# platform_smd.net
KiCad netlist of a schematic drawn in EAGLE
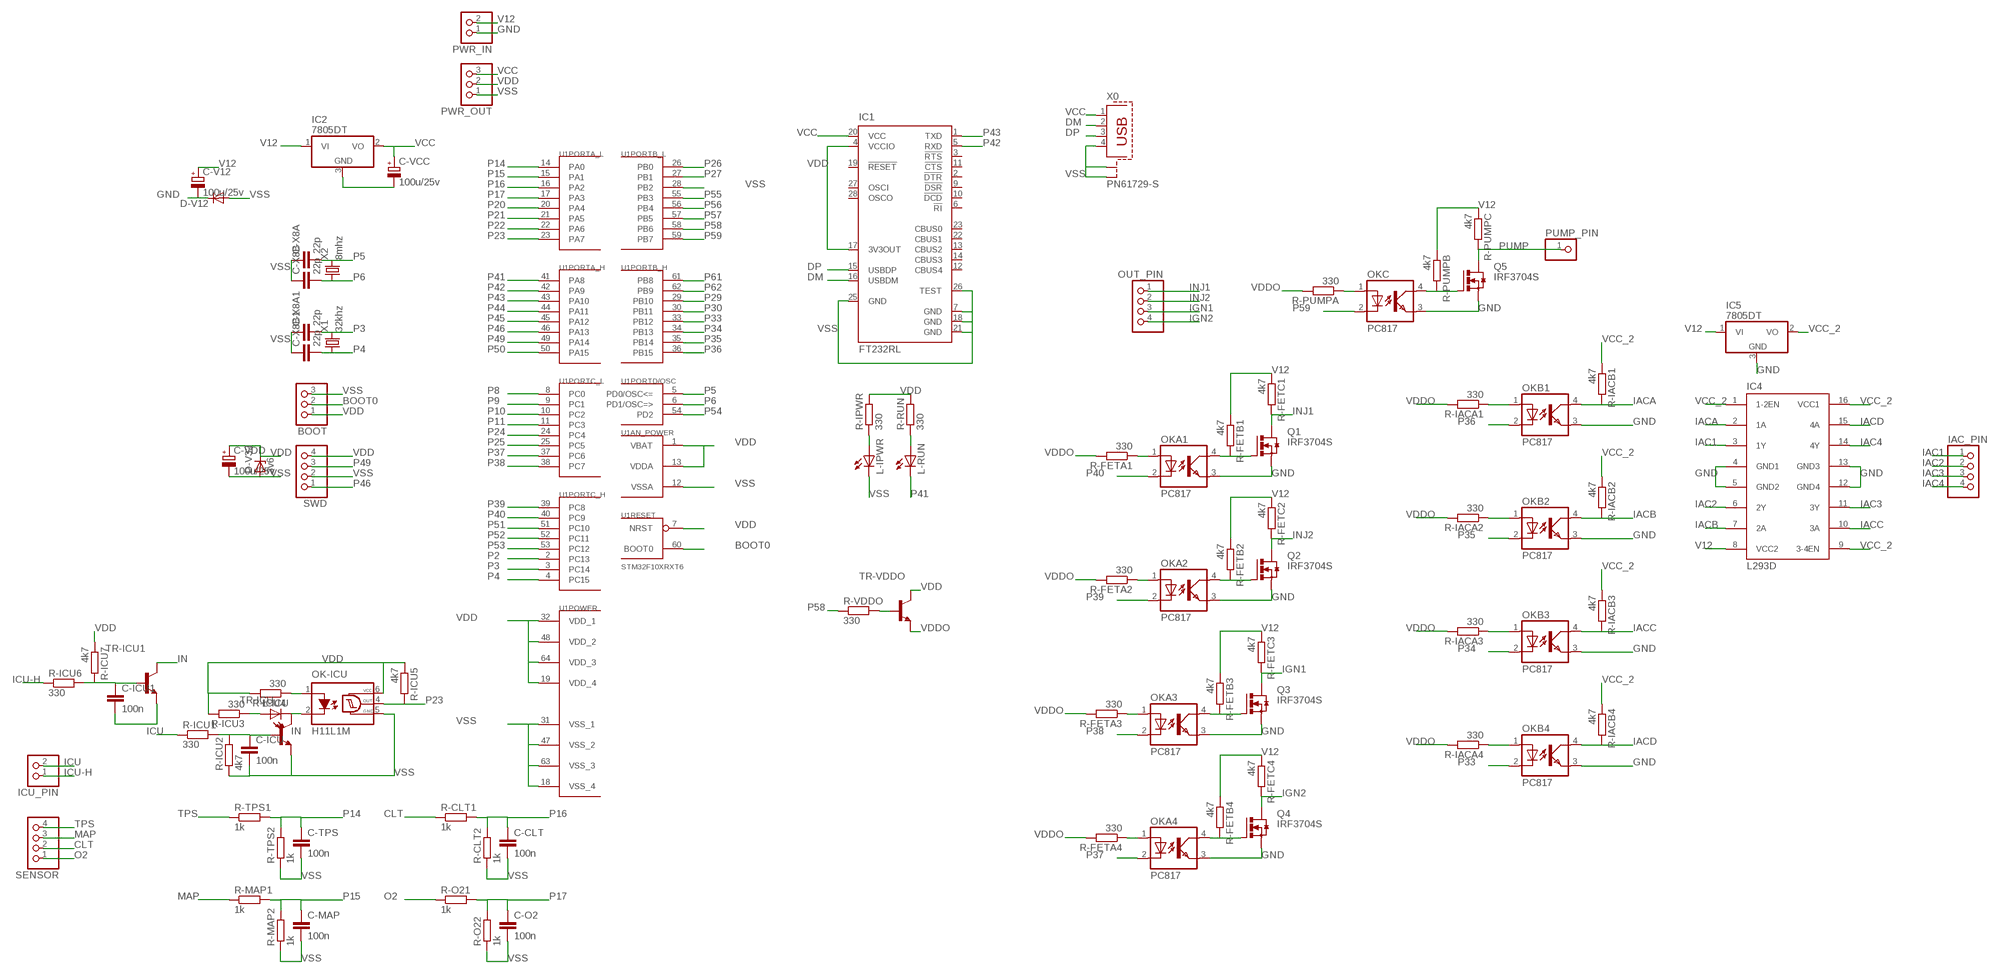
[diagram p0: schematic, sheet 1]

(export (version "E")
  (design (tool "Eeschema 10.0.6"))
  (components
    (comp (ref "BOOT")
      (value "PINHD-1X3")
      (footprint "eagle-import:1X03")
      (libsource (lib "eagle-import") (part "PINHD-1X3"))
    )
    (comp (ref "C-CLT")
      (value "100n")
      (footprint "eagle-import:C0805")
      (libsource (lib "eagle-import") (part "C-EUC0805"))
    )
    (comp (ref "C-ICU")
      (value "100n")
      (footprint "eagle-import:C0805")
      (libsource (lib "eagle-import") (part "C-EUC0805"))
    )
    (comp (ref "C-ICU1")
      (value "100n")
      (footprint "eagle-import:C0805")
      (libsource (lib "eagle-import") (part "C-EUC0805"))
    )
    (comp (ref "C-MAP")
      (value "100n")
      (footprint "eagle-import:C0805")
      (libsource (lib "eagle-import") (part "C-EUC0805"))
    )
    (comp (ref "C-O2")
      (value "100n")
      (footprint "eagle-import:C0805")
      (libsource (lib "eagle-import") (part "C-EUC0805"))
    )
    (comp (ref "C-TPS")
      (value "100n")
      (footprint "eagle-import:C0805")
      (libsource (lib "eagle-import") (part "C-EUC0805"))
    )
    (comp (ref "C-V12")
      (value "100u/25v")
      (footprint "eagle-import:PANASONIC_D")
      (libsource (lib "eagle-import") (part "CPOL-EUD"))
    )
    (comp (ref "C-VCC")
      (value "100u/25v")
      (footprint "eagle-import:PANASONIC_D")
      (libsource (lib "eagle-import") (part "CPOL-EUD"))
    )
    (comp (ref "C-VDD")
      (value "100u/25v")
      (footprint "eagle-import:PANASONIC_D")
      (libsource (lib "eagle-import") (part "CPOL-EUD"))
    )
    (comp (ref "C-X8A")
      (value "22p")
      (footprint "eagle-import:C0805")
      (libsource (lib "eagle-import") (part "C-EUC0805"))
    )
    (comp (ref "C-X8A1")
      (value "22p")
      (footprint "eagle-import:C0805")
      (libsource (lib "eagle-import") (part "C-EUC0805"))
    )
    (comp (ref "C-X8B")
      (value "22p")
      (footprint "eagle-import:C0805")
      (libsource (lib "eagle-import") (part "C-EUC0805"))
    )
    (comp (ref "C-X8B1")
      (value "22p")
      (footprint "eagle-import:C0805")
      (libsource (lib "eagle-import") (part "C-EUC0805"))
    )
    (comp (ref "D-V12")
      (value "DIODE-SMB")
      (footprint "eagle-import:SMB")
      (libsource (lib "eagle-import") (part "DIODE-SMB"))
    )
    (comp (ref "D-V33")
      (value "3v6")
      (footprint "eagle-import:SMB")
      (libsource (lib "eagle-import") (part "ZENER-DIODESMB"))
    )
    (comp (ref "IAC_PIN")
      (value "PINHD-1X4")
      (footprint "eagle-import:1X04")
      (libsource (lib "eagle-import") (part "PINHD-1X4"))
    )
    (comp (ref "IC1")
      (value "FT232RL")
      (footprint "eagle-import:SSOP28")
      (libsource (lib "eagle-import") (part "FT232RL"))
    )
    (comp (ref "IC2")
      (value "7805DT")
      (footprint "eagle-import:TO252")
      (libsource (lib "eagle-import") (part "78DT05"))
    )
    (comp (ref "IC4")
      (value "L293D")
      (footprint "eagle-import:DIL16")
      (libsource (lib "eagle-import") (part "L293D"))
    )
    (comp (ref "IC5")
      (value "7805DT")
      (footprint "eagle-import:TO252")
      (libsource (lib "eagle-import") (part "78DT05"))
    )
    (comp (ref "ICU_PIN")
      (value "PINHD-1X2")
      (footprint "eagle-import:1X02")
      (libsource (lib "eagle-import") (part "PINHD-1X2"))
    )
    (comp (ref "L-ICU")
      (value "LEDSML0805")
      (footprint "eagle-import:SML0805")
      (libsource (lib "eagle-import") (part "LEDSML0805"))
    )
    (comp (ref "L-IPWR")
      (value "LEDSML0805")
      (footprint "eagle-import:SML0805")
      (libsource (lib "eagle-import") (part "LEDSML0805"))
    )
    (comp (ref "L-RUN")
      (value "LEDSML0805")
      (footprint "eagle-import:SML0805")
      (libsource (lib "eagle-import") (part "LEDSML0805"))
    )
    (comp (ref "OK-ICU")
      (value "H11L1M")
      (footprint "eagle-import:DIL06")
      (fields (field (name "MF") "FAIRCHILD SEMICONDUCTOR") (field (name "MPN") "H11L1-M"))
      (libsource (lib "eagle-import") (part "H11LM1"))
    )
    (comp (ref "OKA1")
      (value "PC817")
      (footprint "eagle-import:DIL04")
      (fields (field (name "MPN") "PC817X4J000F"))
      (libsource (lib "eagle-import") (part "PC817"))
    )
    (comp (ref "OKA2")
      (value "PC817")
      (footprint "eagle-import:DIL04")
      (fields (field (name "MPN") "PC817X4J000F"))
      (libsource (lib "eagle-import") (part "PC817"))
    )
    (comp (ref "OKA3")
      (value "PC817")
      (footprint "eagle-import:DIL04")
      (fields (field (name "MPN") "PC817X4J000F"))
      (libsource (lib "eagle-import") (part "PC817"))
    )
    (comp (ref "OKA4")
      (value "PC817")
      (footprint "eagle-import:DIL04")
      (fields (field (name "MPN") "PC817X4J000F"))
      (libsource (lib "eagle-import") (part "PC817"))
    )
    (comp (ref "OKB1")
      (value "PC817")
      (footprint "eagle-import:DIL04")
      (fields (field (name "MPN") "PC817X4J000F"))
      (libsource (lib "eagle-import") (part "PC817"))
    )
    (comp (ref "OKB2")
      (value "PC817")
      (footprint "eagle-import:DIL04")
      (fields (field (name "MPN") "PC817X4J000F"))
      (libsource (lib "eagle-import") (part "PC817"))
    )
    (comp (ref "OKB3")
      (value "PC817")
      (footprint "eagle-import:DIL04")
      (fields (field (name "MPN") "PC817X4J000F"))
      (libsource (lib "eagle-import") (part "PC817"))
    )
    (comp (ref "OKB4")
      (value "PC817")
      (footprint "eagle-import:DIL04")
      (fields (field (name "MPN") "PC817X4J000F"))
      (libsource (lib "eagle-import") (part "PC817"))
    )
    (comp (ref "OKC")
      (value "PC817")
      (footprint "eagle-import:DIL04")
      (fields (field (name "MPN") "PC817X4J000F"))
      (libsource (lib "eagle-import") (part "PC817"))
    )
    (comp (ref "OUT_PIN")
      (value "PINHD-1X4")
      (footprint "eagle-import:1X04")
      (libsource (lib "eagle-import") (part "PINHD-1X4"))
    )
    (comp (ref "PUMP_PIN")
      (value "PINHD-1X1")
      (footprint "eagle-import:1X01")
      (libsource (lib "eagle-import") (part "PINHD-1X1"))
    )
    (comp (ref "PWR_IN")
      (value "PINHD-1X2")
      (footprint "eagle-import:1X02")
      (libsource (lib "eagle-import") (part "PINHD-1X2"))
    )
    (comp (ref "PWR_OUT")
      (value "PINHD-1X3")
      (footprint "eagle-import:1X03")
      (libsource (lib "eagle-import") (part "PINHD-1X3"))
    )
    (comp (ref "Q1")
      (value "IRF3704S")
      (footprint "eagle-import:D2PACK")
      (libsource (lib "eagle-import") (part "IRF3704S"))
    )
    (comp (ref "Q2")
      (value "IRF3704S")
      (footprint "eagle-import:D2PACK")
      (libsource (lib "eagle-import") (part "IRF3704S"))
    )
    (comp (ref "Q3")
      (value "IRF3704S")
      (footprint "eagle-import:D2PACK")
      (libsource (lib "eagle-import") (part "IRF3704S"))
    )
    (comp (ref "Q4")
      (value "IRF3704S")
      (footprint "eagle-import:D2PACK")
      (libsource (lib "eagle-import") (part "IRF3704S"))
    )
    (comp (ref "Q5")
      (value "IRF3704S")
      (footprint "eagle-import:D2PACK")
      (libsource (lib "eagle-import") (part "IRF3704S"))
    )
    (comp (ref "R-CLT1")
      (value "1k")
      (footprint "eagle-import:R0805")
      (libsource (lib "eagle-import") (part "R-EU_R0805"))
    )
    (comp (ref "R-CLT2")
      (value "1k")
      (footprint "eagle-import:R0805")
      (libsource (lib "eagle-import") (part "R-EU_R0805"))
    )
    (comp (ref "R-FETA1")
      (value "330")
      (footprint "eagle-import:R0805")
      (libsource (lib "eagle-import") (part "R-EU_R0805"))
    )
    (comp (ref "R-FETA2")
      (value "330")
      (footprint "eagle-import:R0805")
      (libsource (lib "eagle-import") (part "R-EU_R0805"))
    )
    (comp (ref "R-FETA3")
      (value "330")
      (footprint "eagle-import:R0805")
      (libsource (lib "eagle-import") (part "R-EU_R0805"))
    )
    (comp (ref "R-FETA4")
      (value "330")
      (footprint "eagle-import:R0805")
      (libsource (lib "eagle-import") (part "R-EU_R0805"))
    )
    (comp (ref "R-FETB1")
      (value "4k7")
      (footprint "eagle-import:R0805")
      (libsource (lib "eagle-import") (part "R-EU_R0805"))
    )
    (comp (ref "R-FETB2")
      (value "4k7")
      (footprint "eagle-import:R0805")
      (libsource (lib "eagle-import") (part "R-EU_R0805"))
    )
    (comp (ref "R-FETB3")
      (value "4k7")
      (footprint "eagle-import:R0805")
      (libsource (lib "eagle-import") (part "R-EU_R0805"))
    )
    (comp (ref "R-FETB4")
      (value "4k7")
      (footprint "eagle-import:R0805")
      (libsource (lib "eagle-import") (part "R-EU_R0805"))
    )
    (comp (ref "R-FETC1")
      (value "4k7")
      (footprint "eagle-import:R0805")
      (libsource (lib "eagle-import") (part "R-EU_R0805"))
    )
    (comp (ref "R-FETC2")
      (value "4k7")
      (footprint "eagle-import:R0805")
      (libsource (lib "eagle-import") (part "R-EU_R0805"))
    )
    (comp (ref "R-FETC3")
      (value "4k7")
      (footprint "eagle-import:R0805")
      (libsource (lib "eagle-import") (part "R-EU_R0805"))
    )
    (comp (ref "R-FETC4")
      (value "4k7")
      (footprint "eagle-import:R0805")
      (libsource (lib "eagle-import") (part "R-EU_R0805"))
    )
    (comp (ref "R-IACA1")
      (value "330")
      (footprint "eagle-import:R0805")
      (libsource (lib "eagle-import") (part "R-EU_R0805"))
    )
    (comp (ref "R-IACA2")
      (value "330")
      (footprint "eagle-import:R0805")
      (libsource (lib "eagle-import") (part "R-EU_R0805"))
    )
    (comp (ref "R-IACA3")
      (value "330")
      (footprint "eagle-import:R0805")
      (libsource (lib "eagle-import") (part "R-EU_R0805"))
    )
    (comp (ref "R-IACA4")
      (value "330")
      (footprint "eagle-import:R0805")
      (libsource (lib "eagle-import") (part "R-EU_R0805"))
    )
    (comp (ref "R-IACB1")
      (value "4k7")
      (footprint "eagle-import:R0805")
      (libsource (lib "eagle-import") (part "R-EU_R0805"))
    )
    (comp (ref "R-IACB2")
      (value "4k7")
      (footprint "eagle-import:R0805")
      (libsource (lib "eagle-import") (part "R-EU_R0805"))
    )
    (comp (ref "R-IACB3")
      (value "4k7")
      (footprint "eagle-import:R0805")
      (libsource (lib "eagle-import") (part "R-EU_R0805"))
    )
    (comp (ref "R-IACB4")
      (value "4k7")
      (footprint "eagle-import:R0805")
      (libsource (lib "eagle-import") (part "R-EU_R0805"))
    )
    (comp (ref "R-ICU1")
      (value "330")
      (footprint "eagle-import:R0805")
      (libsource (lib "eagle-import") (part "R-EU_R0805"))
    )
    (comp (ref "R-ICU2")
      (value "4k7")
      (footprint "eagle-import:R0805")
      (libsource (lib "eagle-import") (part "R-EU_R0805"))
    )
    (comp (ref "R-ICU3")
      (value "330")
      (footprint "eagle-import:R0805")
      (libsource (lib "eagle-import") (part "R-EU_R0805"))
    )
    (comp (ref "R-ICU4")
      (value "330")
      (footprint "eagle-import:R0805")
      (libsource (lib "eagle-import") (part "R-EU_R0805"))
    )
    (comp (ref "R-ICU5")
      (value "4k7")
      (footprint "eagle-import:R0805")
      (libsource (lib "eagle-import") (part "R-EU_R0805"))
    )
    (comp (ref "R-ICU6")
      (value "330")
      (footprint "eagle-import:R0805")
      (libsource (lib "eagle-import") (part "R-EU_R0805"))
    )
    (comp (ref "R-ICU7")
      (value "4k7")
      (footprint "eagle-import:R0805")
      (libsource (lib "eagle-import") (part "R-EU_R0805"))
    )
    (comp (ref "R-IPWR")
      (value "330")
      (footprint "eagle-import:R0805")
      (libsource (lib "eagle-import") (part "R-EU_R0805"))
    )
    (comp (ref "R-MAP1")
      (value "1k")
      (footprint "eagle-import:R0805")
      (libsource (lib "eagle-import") (part "R-EU_R0805"))
    )
    (comp (ref "R-MAP2")
      (value "1k")
      (footprint "eagle-import:R0805")
      (libsource (lib "eagle-import") (part "R-EU_R0805"))
    )
    (comp (ref "R-O21")
      (value "1k")
      (footprint "eagle-import:R0805")
      (libsource (lib "eagle-import") (part "R-EU_R0805"))
    )
    (comp (ref "R-O22")
      (value "1k")
      (footprint "eagle-import:R0805")
      (libsource (lib "eagle-import") (part "R-EU_R0805"))
    )
    (comp (ref "R-PUMPA")
      (value "330")
      (footprint "eagle-import:R0805")
      (libsource (lib "eagle-import") (part "R-EU_R0805"))
    )
    (comp (ref "R-PUMPB")
      (value "4k7")
      (footprint "eagle-import:R0805")
      (libsource (lib "eagle-import") (part "R-EU_R0805"))
    )
    (comp (ref "R-PUMPC")
      (value "4k7")
      (footprint "eagle-import:R0805")
      (libsource (lib "eagle-import") (part "R-EU_R0805"))
    )
    (comp (ref "R-RUN")
      (value "330")
      (footprint "eagle-import:R0805")
      (libsource (lib "eagle-import") (part "R-EU_R0805"))
    )
    (comp (ref "R-TPS1")
      (value "1k")
      (footprint "eagle-import:R0805")
      (libsource (lib "eagle-import") (part "R-EU_R0805"))
    )
    (comp (ref "R-TPS2")
      (value "1k")
      (footprint "eagle-import:R0805")
      (libsource (lib "eagle-import") (part "R-EU_R0805"))
    )
    (comp (ref "R-VDDO")
      (value "330")
      (footprint "eagle-import:R0805")
      (libsource (lib "eagle-import") (part "R-EU_R0805"))
    )
    (comp (ref "SENSOR")
      (value "PINHD-1X4")
      (footprint "eagle-import:1X04")
      (libsource (lib "eagle-import") (part "PINHD-1X4"))
    )
    (comp (ref "SWD")
      (value "PINHD-1X4")
      (footprint "eagle-import:1X04")
      (libsource (lib "eagle-import") (part "PINHD-1X4"))
    )
    (comp (ref "TR-ICU")
      (value "MMBT3904LT1-NPN-SOT23-BEC")
      (footprint "eagle-import:SOT23-BEC")
      (libsource (lib "eagle-import") (part "-NPN-SOT23-BECMMBT3904LT1"))
    )
    (comp (ref "TR-ICU1")
      (value "MMBT3904LT1-NPN-SOT23-BEC")
      (footprint "eagle-import:SOT23-BEC")
      (libsource (lib "eagle-import") (part "-NPN-SOT23-BECMMBT3904LT1"))
    )
    (comp (ref "TR-VDDO")
      (value "MMBT3904LT1-NPN-SOT23-BEC")
      (footprint "eagle-import:SOT23-BEC")
      (libsource (lib "eagle-import") (part "-NPN-SOT23-BECMMBT3904LT1"))
    )
    (comp (ref "U1")
      (value "STM32F10XRXT6")
      (footprint "eagle-import:TQFP64")
      (libsource (lib "eagle-import") (part "STM32F10XRXT6"))
    )
    (comp (ref "X0")
      (value "PN61729-S")
      (footprint "eagle-import:PN61729-S")
      (libsource (lib "eagle-import") (part "PN61729-S"))
    )
    (comp (ref "X1")
      (value "32khz")
      (footprint "eagle-import:TC26V")
      (libsource (lib "eagle-import") (part "CRYSTALTC26V"))
    )
    (comp (ref "X2")
      (value "8mhz")
      (footprint "eagle-import:HC49U-V")
      (libsource (lib "eagle-import") (part "CRYSTALHC49U-V"))
    )
  )
  (nets
    (net (code "1") (name "/BOOT0") (class "Default")
      (node (ref "BOOT") (pin "2") (pinfunction "2_2") (pintype "passive"))
      (node (ref "U1") (pin "60") (pinfunction "BOOT0_60") (pintype "input"))
    )
    (net (code "2") (name "/CLT") (class "Default")
      (node (ref "R-CLT1") (pin "1") (pinfunction "1_1") (pintype "passive"))
      (node (ref "SENSOR") (pin "2") (pinfunction "2_2") (pintype "passive"))
    )
    (net (code "3") (name "/DM") (class "Default")
      (node (ref "IC1") (pin "16") (pinfunction "USBDM_16") (pintype "bidirectional"))
      (node (ref "X0") (pin "2") (pinfunction "2_2") (pintype "passive"))
    )
    (net (code "4") (name "/DP") (class "Default")
      (node (ref "IC1") (pin "15") (pinfunction "USBDP_15") (pintype "bidirectional"))
      (node (ref "X0") (pin "3") (pinfunction "3_3") (pintype "passive"))
    )
    (net (code "5") (name "/GND") (class "Default")
      (node (ref "C-V12") (pin "-") (pinfunction "-_-") (pintype "passive"))
      (node (ref "D-V12") (pin "C") (pinfunction "C_C") (pintype "passive"))
      (node (ref "IC4") (pin "12") (pinfunction "GND4_12") (pintype "power_in"))
      (node (ref "IC4") (pin "13") (pinfunction "GND3_13") (pintype "power_in"))
      (node (ref "IC4") (pin "4") (pinfunction "GND1_4") (pintype "power_in"))
      (node (ref "IC4") (pin "5") (pinfunction "GND2_5") (pintype "power_in"))
      (node (ref "IC5") (pin "3") (pinfunction "GND_3") (pintype "passive"))
      (node (ref "OKA1") (pin "3") (pinfunction "EMIT_3") (pintype "passive"))
      (node (ref "OKA2") (pin "3") (pinfunction "EMIT_3") (pintype "passive"))
      (node (ref "OKA3") (pin "3") (pinfunction "EMIT_3") (pintype "passive"))
      (node (ref "OKA4") (pin "3") (pinfunction "EMIT_3") (pintype "passive"))
      (node (ref "OKB1") (pin "3") (pinfunction "EMIT_3") (pintype "passive"))
      (node (ref "OKB2") (pin "3") (pinfunction "EMIT_3") (pintype "passive"))
      (node (ref "OKB3") (pin "3") (pinfunction "EMIT_3") (pintype "passive"))
      (node (ref "OKB4") (pin "3") (pinfunction "EMIT_3") (pintype "passive"))
      (node (ref "OKC") (pin "3") (pinfunction "EMIT_3") (pintype "passive"))
      (node (ref "PWR_IN") (pin "1") (pinfunction "1_1") (pintype "passive"))
      (node (ref "Q1") (pin "3") (pinfunction "S_3") (pintype "passive"))
      (node (ref "Q2") (pin "3") (pinfunction "S_3") (pintype "passive"))
      (node (ref "Q3") (pin "3") (pinfunction "S_3") (pintype "passive"))
      (node (ref "Q4") (pin "3") (pinfunction "S_3") (pintype "passive"))
      (node (ref "Q5") (pin "3") (pinfunction "S_3") (pintype "passive"))
    )
    (net (code "6") (name "/IAC1") (class "Default")
      (node (ref "IAC_PIN") (pin "1") (pinfunction "1_1") (pintype "passive"))
      (node (ref "IC4") (pin "3") (pinfunction "1Y_3") (pintype "output"))
    )
    (net (code "7") (name "/IAC2") (class "Default")
      (node (ref "IAC_PIN") (pin "2") (pinfunction "2_2") (pintype "passive"))
      (node (ref "IC4") (pin "6") (pinfunction "2Y_6") (pintype "output"))
    )
    (net (code "8") (name "/IAC3") (class "Default")
      (node (ref "IAC_PIN") (pin "3") (pinfunction "3_3") (pintype "passive"))
      (node (ref "IC4") (pin "11") (pinfunction "3Y_11") (pintype "output"))
    )
    (net (code "9") (name "/IAC4") (class "Default")
      (node (ref "IAC_PIN") (pin "4") (pinfunction "4_4") (pintype "passive"))
      (node (ref "IC4") (pin "14") (pinfunction "4Y_14") (pintype "output"))
    )
    (net (code "10") (name "/IACA") (class "Default")
      (node (ref "IC4") (pin "2") (pinfunction "1A_2") (pintype "input"))
      (node (ref "OKB1") (pin "4") (pinfunction "COL_4") (pintype "passive"))
      (node (ref "R-IACB1") (pin "2") (pinfunction "2_2") (pintype "passive"))
    )
    (net (code "11") (name "/IACB") (class "Default")
      (node (ref "IC4") (pin "7") (pinfunction "2A_7") (pintype "input"))
      (node (ref "OKB2") (pin "4") (pinfunction "COL_4") (pintype "passive"))
      (node (ref "R-IACB2") (pin "2") (pinfunction "2_2") (pintype "passive"))
    )
    (net (code "12") (name "/IACC") (class "Default")
      (node (ref "IC4") (pin "10") (pinfunction "3A_10") (pintype "input"))
      (node (ref "OKB3") (pin "4") (pinfunction "COL_4") (pintype "passive"))
      (node (ref "R-IACB3") (pin "2") (pinfunction "2_2") (pintype "passive"))
    )
    (net (code "13") (name "/IACD") (class "Default")
      (node (ref "IC4") (pin "15") (pinfunction "4A_15") (pintype "input"))
      (node (ref "OKB4") (pin "4") (pinfunction "COL_4") (pintype "passive"))
      (node (ref "R-IACB4") (pin "2") (pinfunction "2_2") (pintype "passive"))
    )
    (net (code "14") (name "/ICU") (class "Default")
      (node (ref "ICU_PIN") (pin "2") (pinfunction "2_2") (pintype "passive"))
      (node (ref "R-ICU1") (pin "1") (pinfunction "1_1") (pintype "passive"))
    )
    (net (code "15") (name "/ICU-H") (class "Default")
      (node (ref "ICU_PIN") (pin "1") (pinfunction "1_1") (pintype "passive"))
      (node (ref "R-ICU6") (pin "1") (pinfunction "1_1") (pintype "passive"))
    )
    (net (code "16") (name "/IGN1") (class "Default")
      (node (ref "OUT_PIN") (pin "3") (pinfunction "3_3") (pintype "passive"))
      (node (ref "Q3") (pin "2") (pinfunction "D_2") (pintype "passive"))
      (node (ref "R-FETC3") (pin "2") (pinfunction "2_2") (pintype "passive"))
    )
    (net (code "17") (name "/IGN2") (class "Default")
      (node (ref "OUT_PIN") (pin "4") (pinfunction "4_4") (pintype "passive"))
      (node (ref "Q4") (pin "2") (pinfunction "D_2") (pintype "passive"))
      (node (ref "R-FETC4") (pin "2") (pinfunction "2_2") (pintype "passive"))
    )
    (net (code "18") (name "/IN") (class "Default")
      (node (ref "L-ICU") (pin "C") (pinfunction "C_C") (pintype "passive"))
      (node (ref "OK-ICU") (pin "2") (pinfunction "C_2") (pintype "passive"))
      (node (ref "TR-ICU") (pin "C") (pinfunction "C_C") (pintype "passive"))
      (node (ref "TR-ICU1") (pin "C") (pinfunction "C_C") (pintype "passive"))
    )
    (net (code "19") (name "/INJ1") (class "Default")
      (node (ref "OUT_PIN") (pin "1") (pinfunction "1_1") (pintype "passive"))
      (node (ref "Q1") (pin "2") (pinfunction "D_2") (pintype "passive"))
      (node (ref "R-FETC1") (pin "2") (pinfunction "2_2") (pintype "passive"))
    )
    (net (code "20") (name "/INJ2") (class "Default")
      (node (ref "OUT_PIN") (pin "2") (pinfunction "2_2") (pintype "passive"))
      (node (ref "Q2") (pin "2") (pinfunction "D_2") (pintype "passive"))
      (node (ref "R-FETC2") (pin "2") (pinfunction "2_2") (pintype "passive"))
    )
    (net (code "21") (name "/MAP") (class "Default")
      (node (ref "R-MAP1") (pin "1") (pinfunction "1_1") (pintype "passive"))
      (node (ref "SENSOR") (pin "3") (pinfunction "3_3") (pintype "passive"))
    )
    (net (code "22") (name "/O2") (class "Default")
      (node (ref "R-O21") (pin "1") (pinfunction "1_1") (pintype "passive"))
      (node (ref "SENSOR") (pin "1") (pinfunction "1_1") (pintype "passive"))
    )
    (net (code "23") (name "/P2") (class "Default")
      (node (ref "U1") (pin "2") (pinfunction "PC13_2") (pintype "bidirectional"))
    )
    (net (code "24") (name "/P3") (class "Default")
      (node (ref "C-X8A1") (pin "2") (pinfunction "2_2") (pintype "passive"))
      (node (ref "U1") (pin "3") (pinfunction "PC14_3") (pintype "bidirectional"))
      (node (ref "X1") (pin "2") (pinfunction "2_2") (pintype "passive"))
    )
    (net (code "25") (name "/P4") (class "Default")
      (node (ref "C-X8B1") (pin "2") (pinfunction "2_2") (pintype "passive"))
      (node (ref "U1") (pin "4") (pinfunction "PC15_4") (pintype "bidirectional"))
      (node (ref "X1") (pin "1") (pinfunction "1_1") (pintype "passive"))
    )
    (net (code "26") (name "/P5") (class "Default")
      (node (ref "C-X8A") (pin "2") (pinfunction "2_2") (pintype "passive"))
      (node (ref "U1") (pin "5") (pinfunction "PD0/OSC<=_5") (pintype "bidirectional"))
      (node (ref "X2") (pin "2") (pinfunction "2_2") (pintype "passive"))
    )
    (net (code "27") (name "/P6") (class "Default")
      (node (ref "C-X8B") (pin "2") (pinfunction "2_2") (pintype "passive"))
      (node (ref "U1") (pin "6") (pinfunction "PD1/OSC=>_6") (pintype "bidirectional"))
      (node (ref "X2") (pin "1") (pinfunction "1_1") (pintype "passive"))
    )
    (net (code "28") (name "/P8") (class "Default")
      (node (ref "U1") (pin "8") (pinfunction "PC0_8") (pintype "bidirectional"))
    )
    (net (code "29") (name "/P9") (class "Default")
      (node (ref "U1") (pin "9") (pinfunction "PC1_9") (pintype "bidirectional"))
    )
    (net (code "30") (name "/P10") (class "Default")
      (node (ref "U1") (pin "10") (pinfunction "PC2_10") (pintype "bidirectional"))
    )
    (net (code "31") (name "/P11") (class "Default")
      (node (ref "U1") (pin "11") (pinfunction "PC3_11") (pintype "bidirectional"))
    )
    (net (code "32") (name "/P14") (class "Default")
      (node (ref "C-TPS") (pin "1") (pinfunction "1_1") (pintype "passive"))
      (node (ref "R-TPS1") (pin "2") (pinfunction "2_2") (pintype "passive"))
      (node (ref "R-TPS2") (pin "2") (pinfunction "2_2") (pintype "passive"))
      (node (ref "U1") (pin "14") (pinfunction "PA0_14") (pintype "bidirectional"))
    )
    (net (code "33") (name "/P15") (class "Default")
      (node (ref "C-MAP") (pin "1") (pinfunction "1_1") (pintype "passive"))
      (node (ref "R-MAP1") (pin "2") (pinfunction "2_2") (pintype "passive"))
      (node (ref "R-MAP2") (pin "2") (pinfunction "2_2") (pintype "passive"))
      (node (ref "U1") (pin "15") (pinfunction "PA1_15") (pintype "bidirectional"))
    )
    (net (code "34") (name "/P16") (class "Default")
      (node (ref "C-CLT") (pin "1") (pinfunction "1_1") (pintype "passive"))
      (node (ref "R-CLT1") (pin "2") (pinfunction "2_2") (pintype "passive"))
      (node (ref "R-CLT2") (pin "2") (pinfunction "2_2") (pintype "passive"))
      (node (ref "U1") (pin "16") (pinfunction "PA2_16") (pintype "bidirectional"))
    )
    (net (code "35") (name "/P17") (class "Default")
      (node (ref "C-O2") (pin "1") (pinfunction "1_1") (pintype "passive"))
      (node (ref "R-O21") (pin "2") (pinfunction "2_2") (pintype "passive"))
      (node (ref "R-O22") (pin "2") (pinfunction "2_2") (pintype "passive"))
      (node (ref "U1") (pin "17") (pinfunction "PA3_17") (pintype "bidirectional"))
    )
    (net (code "36") (name "/P20") (class "Default")
      (node (ref "U1") (pin "20") (pinfunction "PA4_20") (pintype "bidirectional"))
    )
    (net (code "37") (name "/P21") (class "Default")
      (node (ref "U1") (pin "21") (pinfunction "PA5_21") (pintype "bidirectional"))
    )
    (net (code "38") (name "/P22") (class "Default")
      (node (ref "U1") (pin "22") (pinfunction "PA6_22") (pintype "bidirectional"))
    )
    (net (code "39") (name "/P23") (class "Default")
      (node (ref "OK-ICU") (pin "4") (pinfunction "OUT_4") (pintype "output"))
      (node (ref "R-ICU5") (pin "2") (pinfunction "2_2") (pintype "passive"))
      (node (ref "U1") (pin "23") (pinfunction "PA7_23") (pintype "bidirectional"))
    )
    (net (code "40") (name "/P24") (class "Default")
      (node (ref "U1") (pin "24") (pinfunction "PC4_24") (pintype "bidirectional"))
    )
    (net (code "41") (name "/P25") (class "Default")
      (node (ref "U1") (pin "25") (pinfunction "PC5_25") (pintype "bidirectional"))
    )
    (net (code "42") (name "/P26") (class "Default")
      (node (ref "U1") (pin "26") (pinfunction "PB0_26") (pintype "bidirectional"))
    )
    (net (code "43") (name "/P27") (class "Default")
      (node (ref "U1") (pin "27") (pinfunction "PB1_27") (pintype "bidirectional"))
    )
    (net (code "44") (name "/P29") (class "Default")
      (node (ref "U1") (pin "29") (pinfunction "PB10_29") (pintype "bidirectional"))
    )
    (net (code "45") (name "/P30") (class "Default")
      (node (ref "U1") (pin "30") (pinfunction "PB11_30") (pintype "bidirectional"))
    )
    (net (code "46") (name "/P33") (class "Default")
      (node (ref "OKB4") (pin "2") (pinfunction "C_2") (pintype "passive"))
      (node (ref "U1") (pin "33") (pinfunction "PB12_33") (pintype "bidirectional"))
    )
    (net (code "47") (name "/P34") (class "Default")
      (node (ref "OKB3") (pin "2") (pinfunction "C_2") (pintype "passive"))
      (node (ref "U1") (pin "34") (pinfunction "PB13_34") (pintype "bidirectional"))
    )
    (net (code "48") (name "/P35") (class "Default")
      (node (ref "OKB2") (pin "2") (pinfunction "C_2") (pintype "passive"))
      (node (ref "U1") (pin "35") (pinfunction "PB14_35") (pintype "bidirectional"))
    )
    (net (code "49") (name "/P36") (class "Default")
      (node (ref "OKB1") (pin "2") (pinfunction "C_2") (pintype "passive"))
      (node (ref "U1") (pin "36") (pinfunction "PB15_36") (pintype "bidirectional"))
    )
    (net (code "50") (name "/P37") (class "Default")
      (node (ref "OKA4") (pin "2") (pinfunction "C_2") (pintype "passive"))
      (node (ref "U1") (pin "37") (pinfunction "PC6_37") (pintype "bidirectional"))
    )
    (net (code "51") (name "/P38") (class "Default")
      (node (ref "OKA3") (pin "2") (pinfunction "C_2") (pintype "passive"))
      (node (ref "U1") (pin "38") (pinfunction "PC7_38") (pintype "bidirectional"))
    )
    (net (code "52") (name "/P39") (class "Default")
      (node (ref "OKA2") (pin "2") (pinfunction "C_2") (pintype "passive"))
      (node (ref "U1") (pin "39") (pinfunction "PC8_39") (pintype "bidirectional"))
    )
    (net (code "53") (name "/P40") (class "Default")
      (node (ref "OKA1") (pin "2") (pinfunction "C_2") (pintype "passive"))
      (node (ref "U1") (pin "40") (pinfunction "PC9_40") (pintype "bidirectional"))
    )
    (net (code "54") (name "/P41") (class "Default")
      (node (ref "L-RUN") (pin "C") (pinfunction "C_C") (pintype "passive"))
      (node (ref "U1") (pin "41") (pinfunction "PA8_41") (pintype "bidirectional"))
    )
    (net (code "55") (name "/P42") (class "Default")
      (node (ref "IC1") (pin "5") (pinfunction "RXD_5") (pintype "input"))
      (node (ref "U1") (pin "42") (pinfunction "PA9_42") (pintype "bidirectional"))
    )
    (net (code "56") (name "/P43") (class "Default")
      (node (ref "IC1") (pin "1") (pinfunction "TXD_1") (pintype "output"))
      (node (ref "U1") (pin "43") (pinfunction "PA10_43") (pintype "bidirectional"))
    )
    (net (code "57") (name "/P44") (class "Default")
      (node (ref "U1") (pin "44") (pinfunction "PA11_44") (pintype "bidirectional"))
    )
    (net (code "58") (name "/P45") (class "Default")
      (node (ref "U1") (pin "45") (pinfunction "PA12_45") (pintype "bidirectional"))
    )
    (net (code "59") (name "/P46") (class "Default")
      (node (ref "SWD") (pin "1") (pinfunction "1_1") (pintype "passive"))
      (node (ref "U1") (pin "46") (pinfunction "PA13_46") (pintype "bidirectional"))
    )
    (net (code "60") (name "/P49") (class "Default")
      (node (ref "SWD") (pin "3") (pinfunction "3_3") (pintype "passive"))
      (node (ref "U1") (pin "49") (pinfunction "PA14_49") (pintype "bidirectional"))
    )
    (net (code "61") (name "/P50") (class "Default")
      (node (ref "U1") (pin "50") (pinfunction "PA15_50") (pintype "bidirectional"))
    )
    (net (code "62") (name "/P51") (class "Default")
      (node (ref "U1") (pin "51") (pinfunction "PC10_51") (pintype "bidirectional"))
    )
    (net (code "63") (name "/P52") (class "Default")
      (node (ref "U1") (pin "52") (pinfunction "PC11_52") (pintype "bidirectional"))
    )
    (net (code "64") (name "/P53") (class "Default")
      (node (ref "U1") (pin "53") (pinfunction "PC12_53") (pintype "bidirectional"))
    )
    (net (code "65") (name "/P54") (class "Default")
      (node (ref "U1") (pin "54") (pinfunction "PD2_54") (pintype "bidirectional"))
    )
    (net (code "66") (name "/P55") (class "Default")
      (node (ref "U1") (pin "55") (pinfunction "PB3_55") (pintype "bidirectional"))
    )
    (net (code "67") (name "/P56") (class "Default")
      (node (ref "U1") (pin "56") (pinfunction "PB4_56") (pintype "bidirectional"))
    )
    (net (code "68") (name "/P57") (class "Default")
      (node (ref "U1") (pin "57") (pinfunction "PB5_57") (pintype "bidirectional"))
    )
    (net (code "69") (name "/P58") (class "Default")
      (node (ref "R-VDDO") (pin "1") (pinfunction "1_1") (pintype "passive"))
      (node (ref "U1") (pin "58") (pinfunction "PB6_58") (pintype "bidirectional"))
    )
    (net (code "70") (name "/P59") (class "Default")
      (node (ref "OKC") (pin "2") (pinfunction "C_2") (pintype "passive"))
      (node (ref "U1") (pin "59") (pinfunction "PB7_59") (pintype "bidirectional"))
    )
    (net (code "71") (name "/P61") (class "Default")
      (node (ref "U1") (pin "61") (pinfunction "PB8_61") (pintype "bidirectional"))
    )
    (net (code "72") (name "/P62") (class "Default")
      (node (ref "U1") (pin "62") (pinfunction "PB9_62") (pintype "bidirectional"))
    )
    (net (code "73") (name "/PUMP") (class "Default")
      (node (ref "PUMP_PIN") (pin "1") (pinfunction "1_1") (pintype "passive"))
      (node (ref "Q5") (pin "2") (pinfunction "D_2") (pintype "passive"))
      (node (ref "R-PUMPC") (pin "2") (pinfunction "2_2") (pintype "passive"))
    )
    (net (code "74") (name "/TPS") (class "Default")
      (node (ref "R-TPS1") (pin "1") (pinfunction "1_1") (pintype "passive"))
      (node (ref "SENSOR") (pin "4") (pinfunction "4_4") (pintype "passive"))
    )
    (net (code "75") (name "/V12") (class "Default")
      (node (ref "C-V12") (pin "+") (pinfunction "+_+") (pintype "passive"))
      (node (ref "IC2") (pin "1") (pinfunction "VI_1") (pintype "input"))
      (node (ref "IC4") (pin "8") (pinfunction "VCC2_8") (pintype "power_in"))
      (node (ref "IC5") (pin "1") (pinfunction "VI_1") (pintype "input"))
      (node (ref "PWR_IN") (pin "2") (pinfunction "2_2") (pintype "passive"))
      (node (ref "R-FETB1") (pin "1") (pinfunction "1_1") (pintype "passive"))
      (node (ref "R-FETB2") (pin "1") (pinfunction "1_1") (pintype "passive"))
      (node (ref "R-FETB3") (pin "1") (pinfunction "1_1") (pintype "passive"))
      (node (ref "R-FETB4") (pin "1") (pinfunction "1_1") (pintype "passive"))
      (node (ref "R-FETC1") (pin "1") (pinfunction "1_1") (pintype "passive"))
      (node (ref "R-FETC2") (pin "1") (pinfunction "1_1") (pintype "passive"))
      (node (ref "R-FETC3") (pin "1") (pinfunction "1_1") (pintype "passive"))
      (node (ref "R-FETC4") (pin "1") (pinfunction "1_1") (pintype "passive"))
      (node (ref "R-PUMPB") (pin "1") (pinfunction "1_1") (pintype "passive"))
      (node (ref "R-PUMPC") (pin "1") (pinfunction "1_1") (pintype "passive"))
    )
    (net (code "76") (name "/VCC") (class "Default")
      (node (ref "C-VCC") (pin "+") (pinfunction "+_+") (pintype "passive"))
      (node (ref "IC1") (pin "20") (pinfunction "VCC_20") (pintype "power_in"))
      (node (ref "IC2") (pin "2") (pinfunction "VO_2") (pintype "passive"))
      (node (ref "PWR_OUT") (pin "3") (pinfunction "3_3") (pintype "passive"))
      (node (ref "X0") (pin "1") (pinfunction "1_1") (pintype "passive"))
    )
    (net (code "77") (name "/VCC_2") (class "Default")
      (node (ref "IC4") (pin "1") (pinfunction "1-2EN_1") (pintype "input"))
      (node (ref "IC4") (pin "16") (pinfunction "VCC1_16") (pintype "power_in"))
      (node (ref "IC4") (pin "9") (pinfunction "3-4EN_9") (pintype "input"))
      (node (ref "IC5") (pin "2") (pinfunction "VO_2") (pintype "passive"))
      (node (ref "R-IACB1") (pin "1") (pinfunction "1_1") (pintype "passive"))
      (node (ref "R-IACB2") (pin "1") (pinfunction "1_1") (pintype "passive"))
      (node (ref "R-IACB3") (pin "1") (pinfunction "1_1") (pintype "passive"))
      (node (ref "R-IACB4") (pin "1") (pinfunction "1_1") (pintype "passive"))
    )
    (net (code "78") (name "/VDD") (class "Default")
      (node (ref "BOOT") (pin "1") (pinfunction "1_1") (pintype "passive"))
      (node (ref "C-VDD") (pin "+") (pinfunction "+_+") (pintype "passive"))
      (node (ref "D-V33") (pin "C") (pinfunction "C_C") (pintype "passive"))
      (node (ref "IC1") (pin "17") (pinfunction "3V3OUT_17") (pintype "output"))
      (node (ref "IC1") (pin "4") (pinfunction "VCCIO_4") (pintype "power_in"))
      (node (ref "OK-ICU") (pin "6") (pinfunction "VCC_6") (pintype "power_in"))
      (node (ref "PWR_OUT") (pin "2") (pinfunction "2_2") (pintype "passive"))
      (node (ref "R-ICU3") (pin "2") (pinfunction "2_2") (pintype "passive"))
      (node (ref "R-ICU4") (pin "2") (pinfunction "2_2") (pintype "passive"))
      (node (ref "R-ICU5") (pin "1") (pinfunction "1_1") (pintype "passive"))
      (node (ref "R-ICU7") (pin "1") (pinfunction "1_1") (pintype "passive"))
      (node (ref "R-IPWR") (pin "2") (pinfunction "2_2") (pintype "passive"))
      (node (ref "R-RUN") (pin "2") (pinfunction "2_2") (pintype "passive"))
      (node (ref "SWD") (pin "4") (pinfunction "4_4") (pintype "passive"))
      (node (ref "TR-VDDO") (pin "C") (pinfunction "C_C") (pintype "passive"))
      (node (ref "U1") (pin "1") (pinfunction "VBAT_1") (pintype "power_in"))
      (node (ref "U1") (pin "13") (pinfunction "VDDA_13") (pintype "power_in"))
      (node (ref "U1") (pin "19") (pinfunction "VDD_4_19") (pintype "power_in"))
      (node (ref "U1") (pin "32") (pinfunction "VDD_1_32") (pintype "power_in"))
      (node (ref "U1") (pin "48") (pinfunction "VDD_2_48") (pintype "power_in"))
      (node (ref "U1") (pin "64") (pinfunction "VDD_3_64") (pintype "power_in"))
      (node (ref "U1") (pin "7") (pinfunction "NRST_7") (pintype "input"))
    )
    (net (code "79") (name "/VDDO") (class "Default")
      (node (ref "R-FETA1") (pin "2") (pinfunction "2_2") (pintype "passive"))
      (node (ref "R-FETA2") (pin "2") (pinfunction "2_2") (pintype "passive"))
      (node (ref "R-FETA3") (pin "2") (pinfunction "2_2") (pintype "passive"))
      (node (ref "R-FETA4") (pin "2") (pinfunction "2_2") (pintype "passive"))
      (node (ref "R-IACA1") (pin "2") (pinfunction "2_2") (pintype "passive"))
      (node (ref "R-IACA2") (pin "2") (pinfunction "2_2") (pintype "passive"))
      (node (ref "R-IACA3") (pin "2") (pinfunction "2_2") (pintype "passive"))
      (node (ref "R-IACA4") (pin "2") (pinfunction "2_2") (pintype "passive"))
      (node (ref "R-PUMPA") (pin "2") (pinfunction "2_2") (pintype "passive"))
      (node (ref "TR-VDDO") (pin "E") (pinfunction "E_E") (pintype "passive"))
    )
    (net (code "80") (name "/VSS") (class "Default")
      (node (ref "BOOT") (pin "3") (pinfunction "3_3") (pintype "passive"))
      (node (ref "C-CLT") (pin "2") (pinfunction "2_2") (pintype "passive"))
      (node (ref "C-ICU") (pin "2") (pinfunction "2_2") (pintype "passive"))
      (node (ref "C-MAP") (pin "2") (pinfunction "2_2") (pintype "passive"))
      (node (ref "C-O2") (pin "2") (pinfunction "2_2") (pintype "passive"))
      (node (ref "C-TPS") (pin "2") (pinfunction "2_2") (pintype "passive"))
      (node (ref "C-VCC") (pin "-") (pinfunction "-_-") (pintype "passive"))
      (node (ref "C-VDD") (pin "-") (pinfunction "-_-") (pintype "passive"))
      (node (ref "C-X8A") (pin "1") (pinfunction "1_1") (pintype "passive"))
      (node (ref "C-X8A1") (pin "1") (pinfunction "1_1") (pintype "passive"))
      (node (ref "C-X8B") (pin "1") (pinfunction "1_1") (pintype "passive"))
      (node (ref "C-X8B1") (pin "1") (pinfunction "1_1") (pintype "passive"))
      (node (ref "D-V12") (pin "A") (pinfunction "A_A") (pintype "passive"))
      (node (ref "D-V33") (pin "A") (pinfunction "A_A") (pintype "passive"))
      (node (ref "IC1") (pin "18") (pinfunction "GND_18") (pintype "power_in"))
      (node (ref "IC1") (pin "21") (pinfunction "GND_21") (pintype "power_in"))
      (node (ref "IC1") (pin "25") (pinfunction "GND_25") (pintype "power_in"))
      (node (ref "IC1") (pin "26") (pinfunction "TEST_26") (pintype "input"))
      (node (ref "IC1") (pin "7") (pinfunction "GND_7") (pintype "power_in"))
      (node (ref "IC2") (pin "3") (pinfunction "GND_3") (pintype "passive"))
      (node (ref "L-IPWR") (pin "C") (pinfunction "C_C") (pintype "passive"))
      (node (ref "OK-ICU") (pin "5") (pinfunction "GND_5") (pintype "power_in"))
      (node (ref "PWR_OUT") (pin "1") (pinfunction "1_1") (pintype "passive"))
      (node (ref "R-CLT2") (pin "1") (pinfunction "1_1") (pintype "passive"))
      (node (ref "R-ICU2") (pin "1") (pinfunction "1_1") (pintype "passive"))
      (node (ref "R-MAP2") (pin "1") (pinfunction "1_1") (pintype "passive"))
      (node (ref "R-O22") (pin "1") (pinfunction "1_1") (pintype "passive"))
      (node (ref "R-TPS2") (pin "1") (pinfunction "1_1") (pintype "passive"))
      (node (ref "SWD") (pin "2") (pinfunction "2_2") (pintype "passive"))
      (node (ref "TR-ICU") (pin "E") (pinfunction "E_E") (pintype "passive"))
      (node (ref "U1") (pin "12") (pinfunction "VSSA_12") (pintype "power_in"))
      (node (ref "U1") (pin "18") (pinfunction "VSS_4_18") (pintype "power_in"))
      (node (ref "U1") (pin "28") (pinfunction "PB2_28") (pintype "bidirectional"))
      (node (ref "U1") (pin "31") (pinfunction "VSS_1_31") (pintype "power_in"))
      (node (ref "U1") (pin "47") (pinfunction "VSS_2_47") (pintype "power_in"))
      (node (ref "U1") (pin "63") (pinfunction "VSS_3_63") (pintype "power_in"))
      (node (ref "X0") (pin "4") (pinfunction "4_4") (pintype "passive"))
      (node (ref "X0") (pin "S1") (pinfunction "S1_S1") (pintype "passive"))
      (node (ref "X0") (pin "S2") (pinfunction "S2_S2") (pintype "passive"))
    )
    (net (code "81") (name "Net-(C-ICU-Pad1)") (class "Default")
      (node (ref "C-ICU") (pin "1") (pinfunction "1_1") (pintype "passive"))
      (node (ref "R-ICU1") (pin "2") (pinfunction "2_2") (pintype "passive"))
      (node (ref "R-ICU2") (pin "2") (pinfunction "2_2") (pintype "passive"))
      (node (ref "TR-ICU") (pin "B") (pinfunction "B_B") (pintype "passive"))
    )
    (net (code "82") (name "Net-(C-ICU1-Pad1)") (class "Default")
      (node (ref "C-ICU1") (pin "1") (pinfunction "1_1") (pintype "passive"))
      (node (ref "R-ICU6") (pin "2") (pinfunction "2_2") (pintype "passive"))
      (node (ref "R-ICU7") (pin "2") (pinfunction "2_2") (pintype "passive"))
      (node (ref "TR-ICU1") (pin "B") (pinfunction "B_B") (pintype "passive"))
    )
    (net (code "83") (name "Net-(C-ICU1-Pad2)") (class "Default")
      (node (ref "C-ICU1") (pin "2") (pinfunction "2_2") (pintype "passive"))
      (node (ref "TR-ICU1") (pin "E") (pinfunction "E_E") (pintype "passive"))
    )
    (net (code "84") (name "Net-(L-ICU-PadA)") (class "Default")
      (node (ref "L-ICU") (pin "A") (pinfunction "A_A") (pintype "passive"))
      (node (ref "R-ICU3") (pin "1") (pinfunction "1_1") (pintype "passive"))
    )
    (net (code "85") (name "Net-(L-IPWR-PadA)") (class "Default")
      (node (ref "L-IPWR") (pin "A") (pinfunction "A_A") (pintype "passive"))
      (node (ref "R-IPWR") (pin "1") (pinfunction "1_1") (pintype "passive"))
    )
    (net (code "86") (name "Net-(L-RUN-PadA)") (class "Default")
      (node (ref "L-RUN") (pin "A") (pinfunction "A_A") (pintype "passive"))
      (node (ref "R-RUN") (pin "1") (pinfunction "1_1") (pintype "passive"))
    )
    (net (code "87") (name "Net-(OK-ICU-A)") (class "Default")
      (node (ref "OK-ICU") (pin "1") (pinfunction "A_1") (pintype "passive"))
      (node (ref "R-ICU4") (pin "1") (pinfunction "1_1") (pintype "passive"))
    )
    (net (code "88") (name "Net-(OKA1-A)") (class "Default")
      (node (ref "OKA1") (pin "1") (pinfunction "A_1") (pintype "passive"))
      (node (ref "R-FETA1") (pin "1") (pinfunction "1_1") (pintype "passive"))
    )
    (net (code "89") (name "Net-(OKA1-COL)") (class "Default")
      (node (ref "OKA1") (pin "4") (pinfunction "COL_4") (pintype "passive"))
      (node (ref "Q1") (pin "1") (pinfunction "G_1") (pintype "passive"))
      (node (ref "R-FETB1") (pin "2") (pinfunction "2_2") (pintype "passive"))
    )
    (net (code "90") (name "Net-(OKA2-A)") (class "Default")
      (node (ref "OKA2") (pin "1") (pinfunction "A_1") (pintype "passive"))
      (node (ref "R-FETA2") (pin "1") (pinfunction "1_1") (pintype "passive"))
    )
    (net (code "91") (name "Net-(OKA2-COL)") (class "Default")
      (node (ref "OKA2") (pin "4") (pinfunction "COL_4") (pintype "passive"))
      (node (ref "Q2") (pin "1") (pinfunction "G_1") (pintype "passive"))
      (node (ref "R-FETB2") (pin "2") (pinfunction "2_2") (pintype "passive"))
    )
    (net (code "92") (name "Net-(OKA3-A)") (class "Default")
      (node (ref "OKA3") (pin "1") (pinfunction "A_1") (pintype "passive"))
      (node (ref "R-FETA3") (pin "1") (pinfunction "1_1") (pintype "passive"))
    )
    (net (code "93") (name "Net-(OKA3-COL)") (class "Default")
      (node (ref "OKA3") (pin "4") (pinfunction "COL_4") (pintype "passive"))
      (node (ref "Q3") (pin "1") (pinfunction "G_1") (pintype "passive"))
      (node (ref "R-FETB3") (pin "2") (pinfunction "2_2") (pintype "passive"))
    )
    (net (code "94") (name "Net-(OKA4-A)") (class "Default")
      (node (ref "OKA4") (pin "1") (pinfunction "A_1") (pintype "passive"))
      (node (ref "R-FETA4") (pin "1") (pinfunction "1_1") (pintype "passive"))
    )
    (net (code "95") (name "Net-(OKA4-COL)") (class "Default")
      (node (ref "OKA4") (pin "4") (pinfunction "COL_4") (pintype "passive"))
      (node (ref "Q4") (pin "1") (pinfunction "G_1") (pintype "passive"))
      (node (ref "R-FETB4") (pin "2") (pinfunction "2_2") (pintype "passive"))
    )
    (net (code "96") (name "Net-(OKB1-A)") (class "Default")
      (node (ref "OKB1") (pin "1") (pinfunction "A_1") (pintype "passive"))
      (node (ref "R-IACA1") (pin "1") (pinfunction "1_1") (pintype "passive"))
    )
    (net (code "97") (name "Net-(OKB2-A)") (class "Default")
      (node (ref "OKB2") (pin "1") (pinfunction "A_1") (pintype "passive"))
      (node (ref "R-IACA2") (pin "1") (pinfunction "1_1") (pintype "passive"))
    )
    (net (code "98") (name "Net-(OKB3-A)") (class "Default")
      (node (ref "OKB3") (pin "1") (pinfunction "A_1") (pintype "passive"))
      (node (ref "R-IACA3") (pin "1") (pinfunction "1_1") (pintype "passive"))
    )
    (net (code "99") (name "Net-(OKB4-A)") (class "Default")
      (node (ref "OKB4") (pin "1") (pinfunction "A_1") (pintype "passive"))
      (node (ref "R-IACA4") (pin "1") (pinfunction "1_1") (pintype "passive"))
    )
    (net (code "100") (name "Net-(OKC-A)") (class "Default")
      (node (ref "OKC") (pin "1") (pinfunction "A_1") (pintype "passive"))
      (node (ref "R-PUMPA") (pin "1") (pinfunction "1_1") (pintype "passive"))
    )
    (net (code "101") (name "Net-(OKC-COL)") (class "Default")
      (node (ref "OKC") (pin "4") (pinfunction "COL_4") (pintype "passive"))
      (node (ref "Q5") (pin "1") (pinfunction "G_1") (pintype "passive"))
      (node (ref "R-PUMPB") (pin "2") (pinfunction "2_2") (pintype "passive"))
    )
    (net (code "102") (name "Net-(R-VDDO-Pad2)") (class "Default")
      (node (ref "R-VDDO") (pin "2") (pinfunction "2_2") (pintype "passive"))
      (node (ref "TR-VDDO") (pin "B") (pinfunction "B_B") (pintype "passive"))
    )
    (net (code "103") (name "unconnected-(IC1-CBUS0-Pad23)") (class "Default")
      (node (ref "IC1") (pin "23") (pinfunction "CBUS0_23") (pintype "bidirectional"))
    )
    (net (code "104") (name "unconnected-(IC1-CBUS1-Pad22)") (class "Default")
      (node (ref "IC1") (pin "22") (pinfunction "CBUS1_22") (pintype "bidirectional"))
    )
    (net (code "105") (name "unconnected-(IC1-CBUS2-Pad13)") (class "Default")
      (node (ref "IC1") (pin "13") (pinfunction "CBUS2_13") (pintype "bidirectional"))
    )
    (net (code "106") (name "unconnected-(IC1-CBUS3-Pad14)") (class "Default")
      (node (ref "IC1") (pin "14") (pinfunction "CBUS3_14") (pintype "bidirectional"))
    )
    (net (code "107") (name "unconnected-(IC1-CBUS4-Pad12)") (class "Default")
      (node (ref "IC1") (pin "12") (pinfunction "CBUS4_12") (pintype "bidirectional"))
    )
    (net (code "108") (name "unconnected-(IC1-OSCI-Pad27)") (class "Default")
      (node (ref "IC1") (pin "27") (pinfunction "OSCI_27") (pintype "input"))
    )
    (net (code "109") (name "unconnected-(IC1-OSCO-Pad28)") (class "Default")
      (node (ref "IC1") (pin "28") (pinfunction "OSCO_28") (pintype "output"))
    )
    (net (code "110") (name "unconnected-(IC1-~{CTS}-Pad11)") (class "Default")
      (node (ref "IC1") (pin "11") (pinfunction "~{CTS}_11") (pintype "input"))
    )
    (net (code "111") (name "unconnected-(IC1-~{DCD}-Pad10)") (class "Default")
      (node (ref "IC1") (pin "10") (pinfunction "~{DCD}_10") (pintype "input"))
    )
    (net (code "112") (name "unconnected-(IC1-~{DSR}-Pad9)") (class "Default")
      (node (ref "IC1") (pin "9") (pinfunction "~{DSR}_9") (pintype "input"))
    )
    (net (code "113") (name "unconnected-(IC1-~{DTR}-Pad2)") (class "Default")
      (node (ref "IC1") (pin "2") (pinfunction "~{DTR}_2") (pintype "output"))
    )
    (net (code "114") (name "unconnected-(IC1-~{RESET}-Pad19)") (class "Default")
      (node (ref "IC1") (pin "19") (pinfunction "~{RESET}_19") (pintype "input"))
    )
    (net (code "115") (name "unconnected-(IC1-~{RI}-Pad6)") (class "Default")
      (node (ref "IC1") (pin "6") (pinfunction "~{RI}_6") (pintype "input"))
    )
    (net (code "116") (name "unconnected-(IC1-~{RTS}-Pad3)") (class "Default")
      (node (ref "IC1") (pin "3") (pinfunction "~{RTS}_3") (pintype "output"))
    )
  )
)
